# CAN_JTAG_LDO_USB.net
KiCad netlist of a schematic drawn in Altium Designer
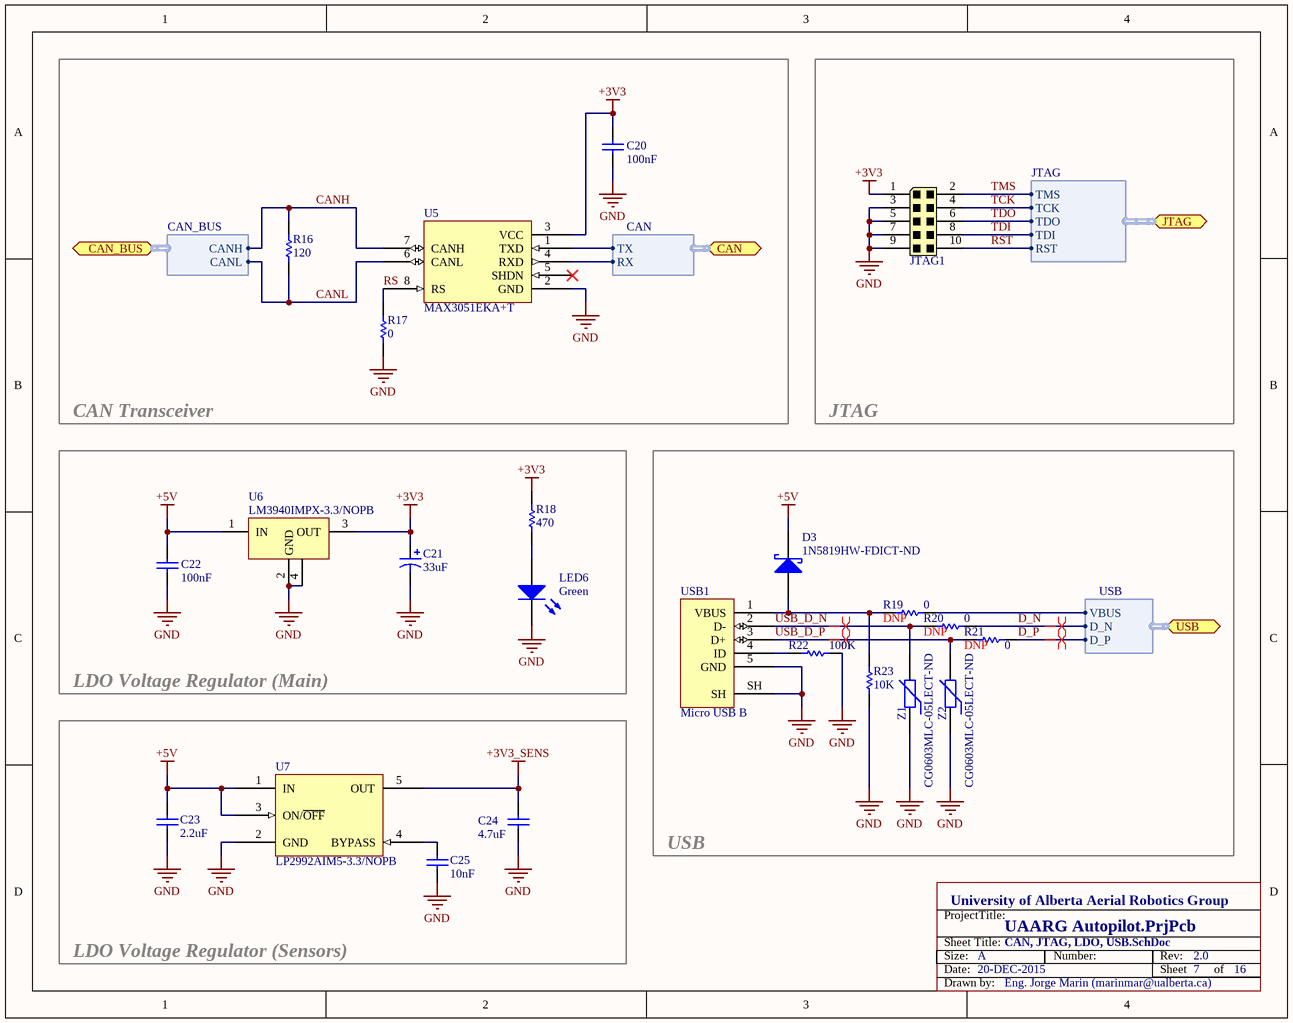
[diagram p0: CAN, JTAG, LDO, USB.SchDoc]

(export (version "E")
  (design (tool "Eeschema 10.0.6"))
  (components
    (comp (ref "C20")
      (value "100nF")
      (footprint "CAP_0402[1005M]")
      (description "Capacitor")
      (fields
        (field (name "MANUFACTURER") "Yageo")
        (field (name "MANUFACTURER PART NUMBER") "CC0402KRX7R6BB104")
      )
      (libsource (lib "UAARG Autopilot") (part "CAP"))
    )
    (comp (ref "C21")
      (value "33uF")
      (footprint "CAPMP3216X16N")
      (description "Polarized Capacitor")
      (fields
        (field (name "MANUFACTURER") "Kemet")
        (field (name "MANUFACTURER PART NUMBER") "T491A336K010AT")
      )
      (libsource (lib "UAARG Autopilot") (part "CAP_POL"))
    )
    (comp (ref "C22")
      (value "100nF")
      (footprint "CAP_0402[1005M]")
      (description "Capacitor")
      (fields
        (field (name "MANUFACTURER") "Yageo")
        (field (name "MANUFACTURER PART NUMBER") "CC0402KRX7R6BB104")
      )
      (libsource (lib "UAARG Autopilot") (part "CAP"))
    )
    (comp (ref "C23")
      (value "2.2uF")
      (footprint "CAP_0402[1005M]")
      (description "Capacitor")
      (fields
        (field (name "MANUFACTURER") "Yageo")
        (field (name "MANUFACTURER PART NUMBER") "CC0402MRX5R5BB225")
      )
      (libsource (lib "UAARG Autopilot") (part "CAP"))
    )
    (comp (ref "C24")
      (value "4.7uF")
      (footprint "CAP_0603[1608M]")
      (description "Capacitor")
      (fields
        (field (name "MANUFACTURER") "Yageo")
        (field (name "MANUFACTURER PART NUMBER") "CC0603KRX5R6BB475")
      )
      (libsource (lib "UAARG Autopilot") (part "CAP"))
    )
    (comp (ref "C25")
      (value "10nF")
      (footprint "CAP_0402[1005M]")
      (description "Capacitor")
      (fields
        (field (name "MANUFACTURER") "Yageo")
        (field (name "MANUFACTURER PART NUMBER") "CC0402KRX7R7BB103")
      )
      (libsource (lib "UAARG Autopilot") (part "CAP"))
    )
    (comp (ref "D3")
      (value "SCHOTTKY DIODE")
      (footprint "SOD-123")
      (description "Typical SchottkyDiode")
      (fields
        (field (name "SUPPLIER PART NUMBER 1") "1N5819HW-FDICT-ND")
        (field (name "MANUFACTURER") "Diodes Incorporated")
        (field (name "MANUFACTURER PART NUMBER") "1N5819HW-7-F")
      )
      (libsource (lib "UAARG Autopilot") (part "SCHOTTKY DIODE"))
    )
    (comp (ref "JTAG1")
      (value "Mini JTAG 5x2 TH")
      (footprint "Header 5x2 1.27mm SMD")
      (description "Mini JTAG connector header 10 pos 5x2 pitch 1.27mm TH")
      (fields
        (field (name "MANUFACTURER") "Samtec Inc.")
        (field (name "MANUFACTURER PART NUMBER") "FTSH-105-01-F-DV-K")
      )
      (libsource (lib "UAARG Autopilot") (part "Mini JTAG 5x2 TH"))
    )
    (comp (ref "LED6")
      (value "LED")
      (footprint "LED_0603[1608M]")
      (description "LED GREEN CLEAR 0603 SMD")
      (fields
        (field (name "MANUFACTURER") "Lite-On Inc.")
        (field (name "MANUFACTURER PART NUMBER") "LTST-C190KGKT")
        (field (name "COLOR") "Green")
      )
      (libsource (lib "UAARG Autopilot") (part "LED"))
    )
    (comp (ref "R16")
      (value "120")
      (footprint "RES_0402[1005M]")
      (description "Resistor")
      (fields
        (field (name "MANUFACTURER") "Yageo")
        (field (name "MANUFACTURER PART NUMBER") "RC0402FR-07120RL")
      )
      (libsource (lib "UAARG Autopilot") (part "RES"))
    )
    (comp (ref "R17")
      (value "0")
      (footprint "RES_0402[1005M]")
      (description "Resistor")
      (fields
        (field (name "MANUFACTURER PART NUMBER") "RC0402JR-070RL")
        (field (name "MANUFACTURER") "Yageo")
      )
      (libsource (lib "UAARG Autopilot") (part "RES"))
    )
    (comp (ref "R18")
      (value "470")
      (footprint "RES_0402[1005M]")
      (description "Resistor")
      (fields
        (field (name "MANUFACTURER PART NUMBER") "RC0402JR-07470RL")
        (field (name "MANUFACTURER") "Yageo")
      )
      (libsource (lib "UAARG Autopilot") (part "RES"))
    )
    (comp (ref "R19")
      (value "0")
      (footprint "RES_0402[1005M]")
      (description "Resistor")
      (fields
        (field (name "MANUFACTURER PART NUMBER") "RC0402JR-070RL")
        (field (name "MANUFACTURER") "Yageo")
        (field (name "NOTE") "DNP")
      )
      (libsource (lib "UAARG Autopilot") (part "RES"))
    )
    (comp (ref "R20")
      (value "0")
      (footprint "RES_0402[1005M]")
      (description "Resistor")
      (fields
        (field (name "MANUFACTURER PART NUMBER") "RC0402JR-070RL")
        (field (name "MANUFACTURER") "Yageo")
        (field (name "NOTE") "DNP")
      )
      (libsource (lib "UAARG Autopilot") (part "RES"))
    )
    (comp (ref "R21")
      (value "0")
      (footprint "RES_0402[1005M]")
      (description "Resistor")
      (fields
        (field (name "MANUFACTURER PART NUMBER") "RC0402JR-070RL")
        (field (name "MANUFACTURER") "Yageo")
        (field (name "NOTE") "DNP")
      )
      (libsource (lib "UAARG Autopilot") (part "RES"))
    )
    (comp (ref "R22")
      (value "100K")
      (footprint "RES_0402[1005M]")
      (description "Resistor")
      (fields
        (field (name "MANUFACTURER") "Yageo")
        (field (name "MANUFACTURER PART NUMBER") "RC0402FR-07100KL")
      )
      (libsource (lib "UAARG Autopilot") (part "RES"))
    )
    (comp (ref "R23")
      (value "10K")
      (footprint "RES_0402[1005M]")
      (description "Resistor")
      (fields
        (field (name "MANUFACTURER") "Yageo")
        (field (name "MANUFACTURER PART NUMBER") "RC0402FR-0710KL")
      )
      (libsource (lib "UAARG Autopilot") (part "RES"))
    )
    (comp (ref "U5")
      (value "MAX3051")
      (footprint "SOT23-8_N")
      (description "MAX3051 CAN Transceiver")
      (fields
        (field (name "MANUFACTURER PART NUMBER") "MAX3051EKA+T")
        (field (name "MANUFACTURER") "Maxim Integrated")
      )
      (libsource (lib "UAARG Autopilot") (part "MAX3051"))
    )
    (comp (ref "U6")
      (value "LM3940IMPX-3.3/NOPB")
      (footprint "SOT223-3")
      (description "IC REG LDO 3.3V 1A SOT223")
      (fields
        (field (name "MANUFACTURER PART NUMBER") "LM3940IMPX-3.3/NOPB")
        (field (name "MANUFACTURER") "Texas Instruments")
      )
      (libsource (lib "UAARG Autopilot") (part "LM3940IMPX-3.3/NOPB"))
    )
    (comp (ref "U7")
      (value "LP2992")
      (footprint "SOT23-5_N")
      (description "LP2992 LDO Voltage Regulator")
      (fields
        (field (name "MANUFACTURER") "Texas Instruments")
        (field (name "MANUFACTURER PART NUMBER") "LP2992AIM5-3.3/NOPB")
      )
      (libsource (lib "UAARG Autopilot") (part "LP2992"))
    )
    (comp (ref "USB1")
      (value "Micro USB B")
      (footprint "Micro USB B_SMT")
      (description "Micro USB Connector Type B")
      (fields
        (field (name "MANUFACTURER PART NUMBER") "0473460001")
        (field (name "MANUFACTURER") "Molex, LLC")
      )
      (libsource (lib "UAARG Autopilot") (part "Micro USB B"))
    )
    (comp (ref "Z1")
      (value "CG0603MLC-05LE")
      (footprint "GEN2_0603[1608M]")
      (description "VARISTOR 0603")
      (fields
        (field (name "SUPPLIER PART NUMBER 1") "CG0603MLC-05LECT-ND")
        (field (name "MANUFACTURER") "Bourns Inc.")
      )
      (libsource (lib "Miscellaneous Devices") (part "Res Varistor"))
    )
    (comp (ref "Z2")
      (value "CG0603MLC-05LE")
      (footprint "GEN2_0603[1608M]")
      (description "VARISTOR 0603")
      (fields
        (field (name "SUPPLIER PART NUMBER 1") "CG0603MLC-05LECT-ND")
        (field (name "MANUFACTURER") "Bourns Inc.")
      )
      (libsource (lib "Miscellaneous Devices") (part "Res Varistor"))
    )
  )
  (nets
    (net (code "5") (name "+3V3") (class "Default")
      (node (ref "C20") (pin "1") (pinfunction "1_1") (pintype "passive"))
      (node (ref "C21") (pin "1") (pinfunction "1_1") (pintype "passive"))
      (node (ref "JTAG1") (pin "1") (pintype "passive"))
      (node (ref "R18") (pin "1") (pinfunction "1_1") (pintype "passive"))
      (node (ref "U5") (pin "3") (pinfunction "VCC_3") (pintype "power_in"))
      (node (ref "U6") (pin "3") (pinfunction "OUT_3") (pintype "power_in"))
    )
    (net (code "6") (name "+3V3_SENS") (class "Default")
      (node (ref "C24") (pin "2") (pinfunction "2_2") (pintype "passive"))
      (node (ref "U7") (pin "5") (pinfunction "OUT_5") (pintype "power_in"))
    )
    (net (code "7") (name "+5V") (class "Default")
      (node (ref "C22") (pin "1") (pinfunction "1_1") (pintype "passive"))
      (node (ref "C23") (pin "2") (pinfunction "2_2") (pintype "passive"))
      (node (ref "D3") (pin "2") (pinfunction "K_2") (pintype "passive"))
      (node (ref "U6") (pin "1") (pinfunction "IN_1") (pintype "power_in"))
      (node (ref "U7") (pin "1") (pinfunction "IN_1") (pintype "power_in"))
      (node (ref "U7") (pin "3") (pinfunction "ON/~{OFF}_3") (pintype "input"))
    )
    (net (code "8") (name "/CANH") (class "Default")
      (node (ref "R16") (pin "2") (pinfunction "2_2") (pintype "passive"))
      (node (ref "U5") (pin "7") (pinfunction "CANH_7") (pintype "bidirectional"))
    )
    (net (code "9") (name "/CANL") (class "Default")
      (node (ref "R16") (pin "1") (pinfunction "1_1") (pintype "passive"))
      (node (ref "U5") (pin "6") (pinfunction "CANL_6") (pintype "bidirectional"))
    )
    (net (code "10") (name "/D_N") (class "Default")
      (node (ref "R20") (pin "1") (pinfunction "1_1") (pintype "passive"))
    )
    (net (code "11") (name "/D_P") (class "Default")
      (node (ref "R21") (pin "1") (pinfunction "1_1") (pintype "passive"))
    )
    (net (code "12") (name "/RS") (class "Default")
      (node (ref "R17") (pin "2") (pinfunction "2_2") (pintype "passive"))
      (node (ref "U5") (pin "8") (pinfunction "RS_8") (pintype "input"))
    )
    (net (code "13") (name "/RST") (class "Default") (node (ref "JTAG1") (pin "10") (pintype "passive")))
    (net (code "14") (name "/RX") (class "Default")
      (node (ref "U5") (pin "4") (pinfunction "RXD_4") (pintype "output"))
    )
    (net (code "15") (name "/TCK") (class "Default") (node (ref "JTAG1") (pin "4") (pintype "passive")))
    (net (code "16") (name "/TDI") (class "Default") (node (ref "JTAG1") (pin "8") (pintype "passive")))
    (net (code "17") (name "/TDO") (class "Default") (node (ref "JTAG1") (pin "6") (pintype "passive")))
    (net (code "18") (name "/TMS") (class "Default") (node (ref "JTAG1") (pin "2") (pintype "passive")))
    (net (code "19") (name "/TX") (class "Default")
      (node (ref "U5") (pin "1") (pinfunction "TXD_1") (pintype "input"))
    )
    (net (code "20") (name "/USB_D_N") (class "Default")
      (node (ref "R20") (pin "2") (pinfunction "2_2") (pintype "passive"))
      (node (ref "USB1") (pin "2") (pinfunction "D-_2") (pintype "bidirectional"))
      (node (ref "Z1") (pin "2") (pinfunction "2_2") (pintype "passive"))
    )
    (net (code "21") (name "/USB_D_P") (class "Default")
      (node (ref "R21") (pin "2") (pinfunction "2_2") (pintype "passive"))
      (node (ref "USB1") (pin "3") (pinfunction "D+_3") (pintype "bidirectional"))
      (node (ref "Z2") (pin "2") (pinfunction "2_2") (pintype "passive"))
    )
    (net (code "22") (name "/VBUS") (class "Default")
      (node (ref "R19") (pin "2") (pinfunction "2_2") (pintype "passive"))
    )
    (net (code "27") (name "GND") (class "Default")
      (node (ref "C20") (pin "2") (pinfunction "2_2") (pintype "passive"))
      (node (ref "C21") (pin "2") (pinfunction "2_2") (pintype "passive"))
      (node (ref "C22") (pin "2") (pinfunction "2_2") (pintype "passive"))
      (node (ref "C23") (pin "1") (pinfunction "1_1") (pintype "passive"))
      (node (ref "C24") (pin "1") (pinfunction "1_1") (pintype "passive"))
      (node (ref "C25") (pin "2") (pinfunction "2_2") (pintype "passive"))
      (node (ref "JTAG1") (pin "3") (pintype "passive"))
      (node (ref "JTAG1") (pin "5") (pintype "passive"))
      (node (ref "JTAG1") (pin "7") (pintype "passive"))
      (node (ref "JTAG1") (pin "9") (pintype "passive"))
      (node (ref "LED6") (pin "2") (pinfunction "K_2") (pintype "passive"))
      (node (ref "R17") (pin "1") (pinfunction "1_1") (pintype "passive"))
      (node (ref "R22") (pin "1") (pinfunction "1_1") (pintype "passive"))
      (node (ref "R23") (pin "1") (pinfunction "1_1") (pintype "passive"))
      (node (ref "U5") (pin "2") (pinfunction "GND_2") (pintype "power_in"))
      (node (ref "U6") (pin "2") (pinfunction "GND_2") (pintype "power_in"))
      (node (ref "U6") (pin "4") (pinfunction "TAB_4") (pintype "power_in"))
      (node (ref "U7") (pin "2") (pinfunction "GND_2") (pintype "power_in"))
      (node (ref "USB1") (pin "5") (pinfunction "GND_5") (pintype "power_in"))
      (node (ref "USB1") (pin "SH") (pinfunction "SH_SH") (pintype "passive"))
      (node (ref "Z1") (pin "1") (pinfunction "1_1") (pintype "passive"))
      (node (ref "Z2") (pin "1") (pinfunction "1_1") (pintype "passive"))
    )
    (net (code "28") (name "Net-(D3-A)") (class "Default")
      (node (ref "D3") (pin "1") (pinfunction "A_1") (pintype "passive"))
      (node (ref "R19") (pin "1") (pinfunction "1_1") (pintype "passive"))
      (node (ref "R23") (pin "2") (pinfunction "2_2") (pintype "passive"))
      (node (ref "USB1") (pin "1") (pinfunction "VBUS_1") (pintype "power_in"))
    )
    (net (code "29") (name "Net-(LED6-A)") (class "Default")
      (node (ref "LED6") (pin "1") (pinfunction "A_1") (pintype "passive"))
      (node (ref "R18") (pin "2") (pinfunction "2_2") (pintype "passive"))
    )
    (net (code "30") (name "Net-(U7-BYPASS)") (class "Default")
      (node (ref "C25") (pin "1") (pinfunction "1_1") (pintype "passive"))
      (node (ref "U7") (pin "4") (pinfunction "BYPASS_4") (pintype "input"))
    )
    (net (code "31") (name "Net-(USB1-ID)") (class "Default")
      (node (ref "R22") (pin "2") (pinfunction "2_2") (pintype "passive"))
      (node (ref "USB1") (pin "4") (pinfunction "ID_4") (pintype "passive"))
    )
    (net (code "32") (name "unconnected-(U5-SHDN-Pad5)") (class "Default")
      (node (ref "U5") (pin "5") (pinfunction "SHDN_5") (pintype "input+no_connect"))
    )
  )
)
